# ECG_FILTER.net
KiCad netlist of a schematic drawn in Altium Designer
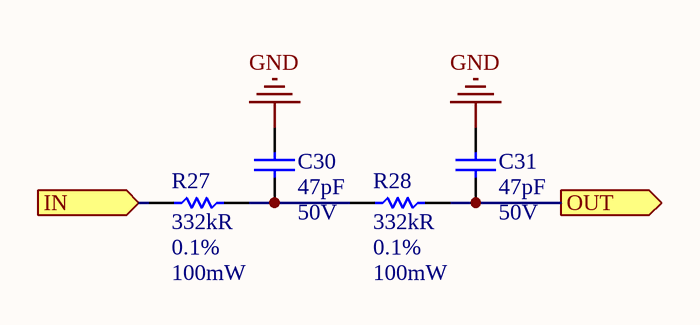
[diagram p0: ECG FILTER.SchDoc]

(export (version "E")
  (design (tool "Eeschema 10.0.6"))
  (components
    (comp (ref "C30")
      (value "MCMT15N470F500CT")
      (footprint "0402 CAPACITOR")
      (description "Cap Ceramic 47pF 50V C0G 1% SMD 0402 125°C")
      (fields
        (field (name "CAPACITANCE") "47pF")
        (field (name "VOLTAGE RATING") "50V")
        (field (name "TOLERANCE") "1%")
      )
      (libsource (lib "Premier EDA Student Advantage Programme") (part "Capacitor"))
    )
    (comp (ref "C31")
      (value "MCMT15N470F500CT")
      (footprint "0402 CAPACITOR")
      (description "Cap Ceramic 47pF 50V C0G 1% SMD 0402 125°C")
      (fields
        (field (name "CAPACITANCE") "47pF")
        (field (name "VOLTAGE RATING") "50V")
        (field (name "TOLERANCE") "1%")
      )
      (libsource (lib "Premier EDA Student Advantage Programme") (part "Capacitor"))
    )
    (comp (ref "R27")
      (value "MCT06030E3323BP100")
      (footprint "MCT06030E3323BP100")
      (description "Surface Mount Thin Film Resistor, Mct Series, 332 Kohm, 100 Mw, - 0.1%, 75 V Rohs Compliant: Yes")
      (fields
        (field (name "RESISTANCE") "332kR")
        (field (name "TOLERANCE") "0.1%")
        (field (name "POWER RATING") "100mW")
      )
      (libsource (lib "Premier EDA Student Advantage Programme") (part "Resistor"))
    )
    (comp (ref "R28")
      (value "MCT06030E3323BP100")
      (footprint "MCT06030E3323BP100")
      (description "Surface Mount Thin Film Resistor, Mct Series, 332 Kohm, 100 Mw, - 0.1%, 75 V Rohs Compliant: Yes")
      (fields
        (field (name "RESISTANCE") "332kR")
        (field (name "TOLERANCE") "0.1%")
        (field (name "POWER RATING") "100mW")
      )
      (libsource (lib "Premier EDA Student Advantage Programme") (part "Resistor"))
    )
  )
  (nets
    (net (code "1") (name "/IN") (class "Default")
      (node (ref "R27") (pin "1") (pinfunction "1_1") (pintype "power_in"))
    )
    (net (code "2") (name "/OUT") (class "Default")
      (node (ref "C31") (pin "1") (pinfunction "1_1") (pintype "power_in"))
      (node (ref "R28") (pin "2") (pinfunction "2_2") (pintype "power_in"))
    )
    (net (code "3") (name "GND") (class "Default")
      (node (ref "C30") (pin "2") (pinfunction "2_2") (pintype "power_in"))
      (node (ref "C31") (pin "2") (pinfunction "2_2") (pintype "power_in"))
    )
    (net (code "4") (name "Net-(C30-Pad1)") (class "Default")
      (node (ref "C30") (pin "1") (pinfunction "1_1") (pintype "power_in"))
      (node (ref "R27") (pin "2") (pinfunction "2_2") (pintype "power_in"))
      (node (ref "R28") (pin "1") (pinfunction "1_1") (pintype "power_in"))
    )
  )
)
